# NixieClockDisplay.net
KiCad netlist of a schematic drawn in EAGLE
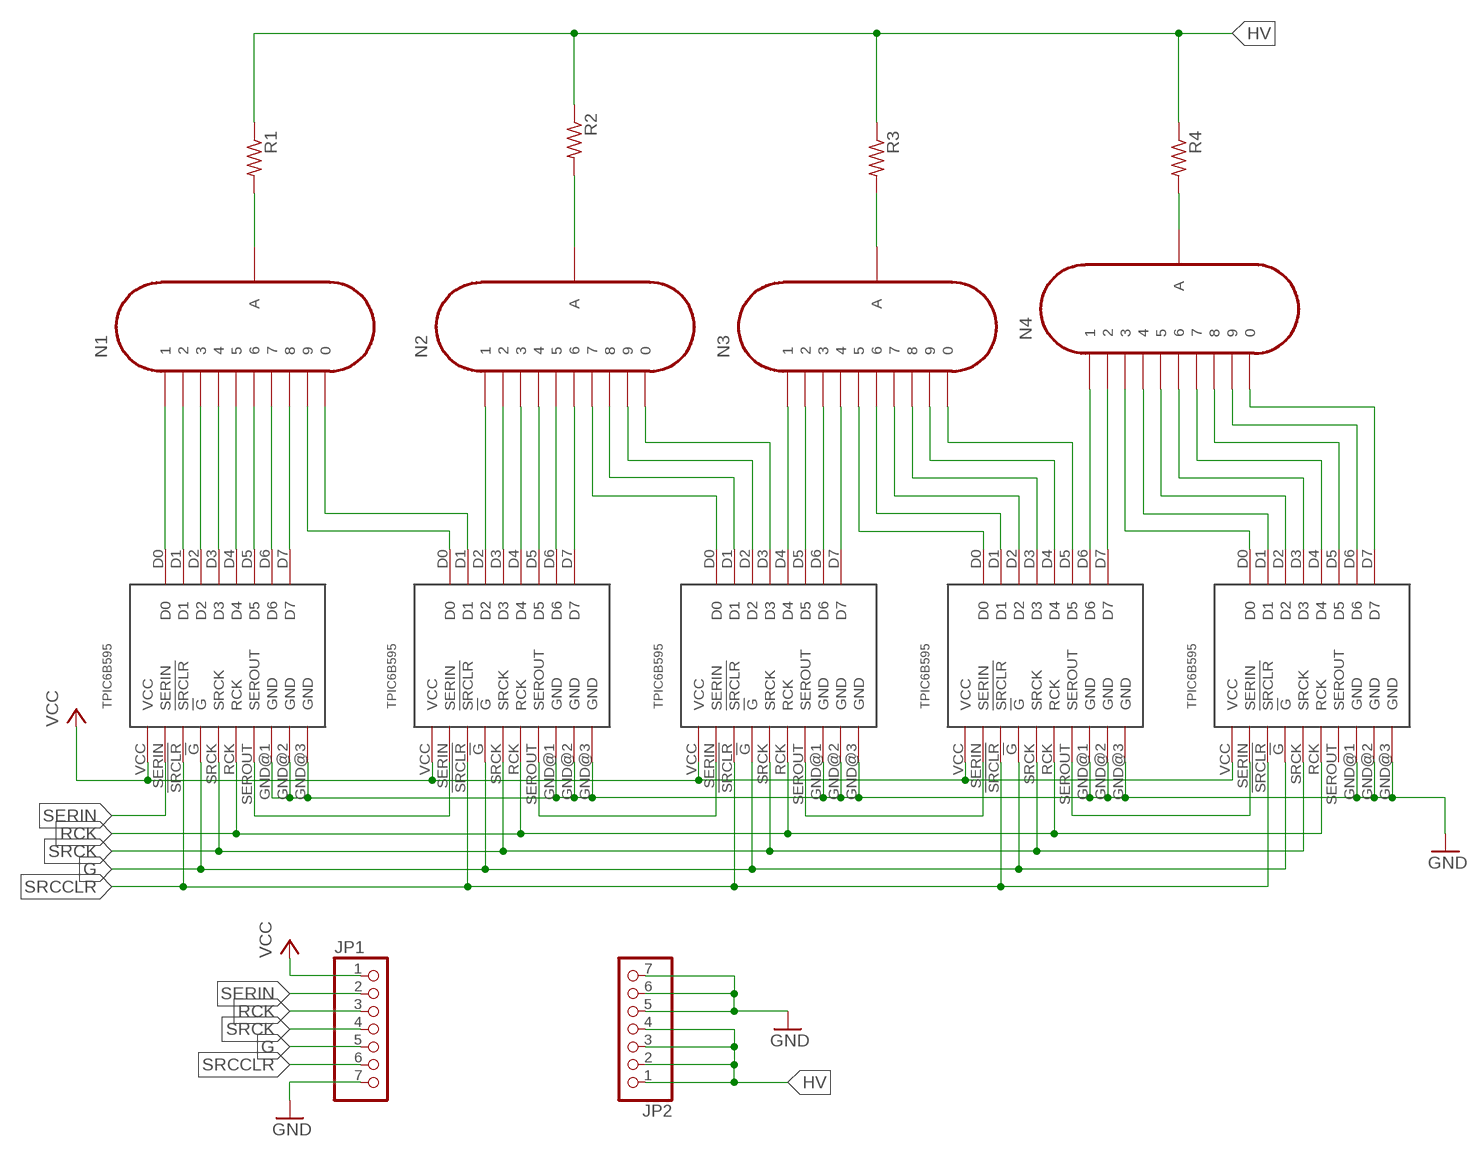
[diagram p0: schematic, sheet 1]

(export (version "E")
  (design (tool "Eeschema 10.0.6"))
  (components
    (comp (ref "JP1")
      (value "PINHD-1X7")
      (footprint "eagle-import:1X07")
      (libsource (lib "eagle-import") (part "PINHD-1X7"))
    )
    (comp (ref "JP2")
      (value "PINHD-1X7")
      (footprint "eagle-import:1X07")
      (libsource (lib "eagle-import") (part "PINHD-1X7"))
    )
    (comp (ref "N1")
      (value "IN-12A")
      (footprint "eagle-import:IN-12")
      (libsource (lib "eagle-import") (part "IN-12A"))
    )
    (comp (ref "N2")
      (value "IN-12A")
      (footprint "eagle-import:IN-12")
      (libsource (lib "eagle-import") (part "IN-12A"))
    )
    (comp (ref "N3")
      (value "IN-12A")
      (footprint "eagle-import:IN-12")
      (libsource (lib "eagle-import") (part "IN-12A"))
    )
    (comp (ref "N4")
      (value "IN-12A")
      (footprint "eagle-import:IN-12")
      (libsource (lib "eagle-import") (part "IN-12A"))
    )
    (comp (ref "R1")
      (value "R-US_0207/10")
      (footprint "eagle-import:0207_10")
      (libsource (lib "eagle-import") (part "R-US_0207/10"))
    )
    (comp (ref "R2")
      (value "R-US_0207/10")
      (footprint "eagle-import:0207_10")
      (libsource (lib "eagle-import") (part "R-US_0207/10"))
    )
    (comp (ref "R3")
      (value "R-US_0207/10")
      (footprint "eagle-import:0207_10")
      (libsource (lib "eagle-import") (part "R-US_0207/10"))
    )
    (comp (ref "R4")
      (value "R-US_0207/10")
      (footprint "eagle-import:0207_10")
      (libsource (lib "eagle-import") (part "R-US_0207/10"))
    )
    (comp (ref "U$1")
      (value "TPIC6B595")
      (footprint "eagle-import:DIL20")
      (libsource (lib "eagle-import") (part "TPIC6B595"))
    )
    (comp (ref "U$2")
      (value "TPIC6B595")
      (footprint "eagle-import:DIL20")
      (libsource (lib "eagle-import") (part "TPIC6B595"))
    )
    (comp (ref "U$3")
      (value "TPIC6B595")
      (footprint "eagle-import:DIL20")
      (libsource (lib "eagle-import") (part "TPIC6B595"))
    )
    (comp (ref "U$4")
      (value "TPIC6B595")
      (footprint "eagle-import:DIL20")
      (libsource (lib "eagle-import") (part "TPIC6B595"))
    )
    (comp (ref "U$5")
      (value "TPIC6B595")
      (footprint "eagle-import:DIL20")
      (libsource (lib "eagle-import") (part "TPIC6B595"))
    )
  )
  (nets
    (net (code "1") (name "G") (class "Default")
      (node (ref "JP1") (pin "5") (pinfunction "5_5") (pintype "passive"))
      (node (ref "U$1") (pin "!G") (pinfunction "~{G}_!G") (pintype "bidirectional"))
      (node (ref "U$2") (pin "!G") (pinfunction "~{G}_!G") (pintype "bidirectional"))
      (node (ref "U$3") (pin "!G") (pinfunction "~{G}_!G") (pintype "bidirectional"))
      (node (ref "U$4") (pin "!G") (pinfunction "~{G}_!G") (pintype "bidirectional"))
      (node (ref "U$5") (pin "!G") (pinfunction "~{G}_!G") (pintype "bidirectional"))
    )
    (net (code "2") (name "GND") (class "Default")
      (node (ref "JP1") (pin "7") (pinfunction "7_7") (pintype "passive"))
      (node (ref "JP2") (pin "5") (pinfunction "5_5") (pintype "passive"))
      (node (ref "JP2") (pin "6") (pinfunction "6_6") (pintype "passive"))
      (node (ref "JP2") (pin "7") (pinfunction "7_7") (pintype "passive"))
      (node (ref "U$1") (pin "GND@1") (pinfunction "GND_GND@1") (pintype "bidirectional"))
      (node (ref "U$1") (pin "GND@2") (pinfunction "GND_GND@2") (pintype "bidirectional"))
      (node (ref "U$1") (pin "GND@3") (pinfunction "GND_GND@3") (pintype "bidirectional"))
      (node (ref "U$2") (pin "GND@1") (pinfunction "GND_GND@1") (pintype "bidirectional"))
      (node (ref "U$2") (pin "GND@2") (pinfunction "GND_GND@2") (pintype "bidirectional"))
      (node (ref "U$2") (pin "GND@3") (pinfunction "GND_GND@3") (pintype "bidirectional"))
      (node (ref "U$3") (pin "GND@1") (pinfunction "GND_GND@1") (pintype "bidirectional"))
      (node (ref "U$3") (pin "GND@2") (pinfunction "GND_GND@2") (pintype "bidirectional"))
      (node (ref "U$3") (pin "GND@3") (pinfunction "GND_GND@3") (pintype "bidirectional"))
      (node (ref "U$4") (pin "GND@1") (pinfunction "GND_GND@1") (pintype "bidirectional"))
      (node (ref "U$4") (pin "GND@2") (pinfunction "GND_GND@2") (pintype "bidirectional"))
      (node (ref "U$4") (pin "GND@3") (pinfunction "GND_GND@3") (pintype "bidirectional"))
      (node (ref "U$5") (pin "GND@1") (pinfunction "GND_GND@1") (pintype "bidirectional"))
      (node (ref "U$5") (pin "GND@2") (pinfunction "GND_GND@2") (pintype "bidirectional"))
      (node (ref "U$5") (pin "GND@3") (pinfunction "GND_GND@3") (pintype "bidirectional"))
    )
    (net (code "3") (name "HV") (class "Default")
      (node (ref "JP2") (pin "1") (pinfunction "1_1") (pintype "passive"))
      (node (ref "JP2") (pin "2") (pinfunction "2_2") (pintype "passive"))
      (node (ref "JP2") (pin "3") (pinfunction "3_3") (pintype "passive"))
      (node (ref "JP2") (pin "4") (pinfunction "4_4") (pintype "passive"))
      (node (ref "R1") (pin "1") (pinfunction "1_1") (pintype "passive"))
      (node (ref "R2") (pin "1") (pinfunction "1_1") (pintype "passive"))
      (node (ref "R3") (pin "1") (pinfunction "1_1") (pintype "passive"))
      (node (ref "R4") (pin "1") (pinfunction "1_1") (pintype "passive"))
    )
    (net (code "4") (name "Net-(N1-Pad0)") (class "Default")
      (node (ref "N1") (pin "0") (pinfunction "0_0") (pintype "bidirectional"))
      (node (ref "U$2") (pin "D1") (pinfunction "D1_D1") (pintype "bidirectional"))
    )
    (net (code "5") (name "Net-(N1-Pad1)") (class "Default")
      (node (ref "N1") (pin "1") (pinfunction "1_1") (pintype "bidirectional"))
      (node (ref "U$1") (pin "D0") (pinfunction "D0_D0") (pintype "bidirectional"))
    )
    (net (code "6") (name "Net-(N1-Pad2)") (class "Default")
      (node (ref "N1") (pin "2") (pinfunction "2_2") (pintype "bidirectional"))
      (node (ref "U$1") (pin "D1") (pinfunction "D1_D1") (pintype "bidirectional"))
    )
    (net (code "7") (name "Net-(N1-Pad3)") (class "Default")
      (node (ref "N1") (pin "3") (pinfunction "3_3") (pintype "bidirectional"))
      (node (ref "U$1") (pin "D2") (pinfunction "D2_D2") (pintype "bidirectional"))
    )
    (net (code "8") (name "Net-(N1-Pad4)") (class "Default")
      (node (ref "N1") (pin "4") (pinfunction "4_4") (pintype "bidirectional"))
      (node (ref "U$1") (pin "D3") (pinfunction "D3_D3") (pintype "bidirectional"))
    )
    (net (code "9") (name "Net-(N1-Pad5)") (class "Default")
      (node (ref "N1") (pin "5") (pinfunction "5_5") (pintype "bidirectional"))
      (node (ref "U$1") (pin "D4") (pinfunction "D4_D4") (pintype "bidirectional"))
    )
    (net (code "10") (name "Net-(N1-Pad6)") (class "Default")
      (node (ref "N1") (pin "6") (pinfunction "6_6") (pintype "bidirectional"))
      (node (ref "U$1") (pin "D5") (pinfunction "D5_D5") (pintype "bidirectional"))
    )
    (net (code "11") (name "Net-(N1-Pad7)") (class "Default")
      (node (ref "N1") (pin "7") (pinfunction "7_7") (pintype "bidirectional"))
      (node (ref "U$1") (pin "D6") (pinfunction "D6_D6") (pintype "bidirectional"))
    )
    (net (code "12") (name "Net-(N1-Pad8)") (class "Default")
      (node (ref "N1") (pin "8") (pinfunction "8_8") (pintype "bidirectional"))
      (node (ref "U$1") (pin "D7") (pinfunction "D7_D7") (pintype "bidirectional"))
    )
    (net (code "13") (name "Net-(N1-Pad9)") (class "Default")
      (node (ref "N1") (pin "9") (pinfunction "9_9") (pintype "bidirectional"))
      (node (ref "U$2") (pin "D0") (pinfunction "D0_D0") (pintype "bidirectional"))
    )
    (net (code "14") (name "Net-(N1-PadA)") (class "Default")
      (node (ref "N1") (pin "A") (pinfunction "A_A") (pintype "bidirectional"))
      (node (ref "R1") (pin "2") (pinfunction "2_2") (pintype "passive"))
    )
    (net (code "15") (name "Net-(N2-Pad0)") (class "Default")
      (node (ref "N2") (pin "0") (pinfunction "0_0") (pintype "bidirectional"))
      (node (ref "U$3") (pin "D3") (pinfunction "D3_D3") (pintype "bidirectional"))
    )
    (net (code "16") (name "Net-(N2-Pad1)") (class "Default")
      (node (ref "N2") (pin "1") (pinfunction "1_1") (pintype "bidirectional"))
      (node (ref "U$2") (pin "D2") (pinfunction "D2_D2") (pintype "bidirectional"))
    )
    (net (code "17") (name "Net-(N2-Pad2)") (class "Default")
      (node (ref "N2") (pin "2") (pinfunction "2_2") (pintype "bidirectional"))
      (node (ref "U$2") (pin "D3") (pinfunction "D3_D3") (pintype "bidirectional"))
    )
    (net (code "18") (name "Net-(N2-Pad3)") (class "Default")
      (node (ref "N2") (pin "3") (pinfunction "3_3") (pintype "bidirectional"))
      (node (ref "U$2") (pin "D4") (pinfunction "D4_D4") (pintype "bidirectional"))
    )
    (net (code "19") (name "Net-(N2-Pad4)") (class "Default")
      (node (ref "N2") (pin "4") (pinfunction "4_4") (pintype "bidirectional"))
      (node (ref "U$2") (pin "D5") (pinfunction "D5_D5") (pintype "bidirectional"))
    )
    (net (code "20") (name "Net-(N2-Pad5)") (class "Default")
      (node (ref "N2") (pin "5") (pinfunction "5_5") (pintype "bidirectional"))
      (node (ref "U$2") (pin "D6") (pinfunction "D6_D6") (pintype "bidirectional"))
    )
    (net (code "21") (name "Net-(N2-Pad6)") (class "Default")
      (node (ref "N2") (pin "6") (pinfunction "6_6") (pintype "bidirectional"))
      (node (ref "U$2") (pin "D7") (pinfunction "D7_D7") (pintype "bidirectional"))
    )
    (net (code "22") (name "Net-(N2-Pad7)") (class "Default")
      (node (ref "N2") (pin "7") (pinfunction "7_7") (pintype "bidirectional"))
      (node (ref "U$3") (pin "D0") (pinfunction "D0_D0") (pintype "bidirectional"))
    )
    (net (code "23") (name "Net-(N2-Pad8)") (class "Default")
      (node (ref "N2") (pin "8") (pinfunction "8_8") (pintype "bidirectional"))
      (node (ref "U$3") (pin "D1") (pinfunction "D1_D1") (pintype "bidirectional"))
    )
    (net (code "24") (name "Net-(N2-Pad9)") (class "Default")
      (node (ref "N2") (pin "9") (pinfunction "9_9") (pintype "bidirectional"))
      (node (ref "U$3") (pin "D2") (pinfunction "D2_D2") (pintype "bidirectional"))
    )
    (net (code "25") (name "Net-(N2-PadA)") (class "Default")
      (node (ref "N2") (pin "A") (pinfunction "A_A") (pintype "bidirectional"))
      (node (ref "R2") (pin "2") (pinfunction "2_2") (pintype "passive"))
    )
    (net (code "26") (name "Net-(N3-Pad0)") (class "Default")
      (node (ref "N3") (pin "0") (pinfunction "0_0") (pintype "bidirectional"))
      (node (ref "U$4") (pin "D5") (pinfunction "D5_D5") (pintype "bidirectional"))
    )
    (net (code "27") (name "Net-(N3-Pad1)") (class "Default")
      (node (ref "N3") (pin "1") (pinfunction "1_1") (pintype "bidirectional"))
      (node (ref "U$3") (pin "D4") (pinfunction "D4_D4") (pintype "bidirectional"))
    )
    (net (code "28") (name "Net-(N3-Pad2)") (class "Default")
      (node (ref "N3") (pin "2") (pinfunction "2_2") (pintype "bidirectional"))
      (node (ref "U$3") (pin "D5") (pinfunction "D5_D5") (pintype "bidirectional"))
    )
    (net (code "29") (name "Net-(N3-Pad3)") (class "Default")
      (node (ref "N3") (pin "3") (pinfunction "3_3") (pintype "bidirectional"))
      (node (ref "U$3") (pin "D6") (pinfunction "D6_D6") (pintype "bidirectional"))
    )
    (net (code "30") (name "Net-(N3-Pad4)") (class "Default")
      (node (ref "N3") (pin "4") (pinfunction "4_4") (pintype "bidirectional"))
      (node (ref "U$3") (pin "D7") (pinfunction "D7_D7") (pintype "bidirectional"))
    )
    (net (code "31") (name "Net-(N3-Pad5)") (class "Default")
      (node (ref "N3") (pin "5") (pinfunction "5_5") (pintype "bidirectional"))
      (node (ref "U$4") (pin "D0") (pinfunction "D0_D0") (pintype "bidirectional"))
    )
    (net (code "32") (name "Net-(N3-Pad6)") (class "Default")
      (node (ref "N3") (pin "6") (pinfunction "6_6") (pintype "bidirectional"))
      (node (ref "U$4") (pin "D1") (pinfunction "D1_D1") (pintype "bidirectional"))
    )
    (net (code "33") (name "Net-(N3-Pad7)") (class "Default")
      (node (ref "N3") (pin "7") (pinfunction "7_7") (pintype "bidirectional"))
      (node (ref "U$4") (pin "D2") (pinfunction "D2_D2") (pintype "bidirectional"))
    )
    (net (code "34") (name "Net-(N3-Pad8)") (class "Default")
      (node (ref "N3") (pin "8") (pinfunction "8_8") (pintype "bidirectional"))
      (node (ref "U$4") (pin "D3") (pinfunction "D3_D3") (pintype "bidirectional"))
    )
    (net (code "35") (name "Net-(N3-Pad9)") (class "Default")
      (node (ref "N3") (pin "9") (pinfunction "9_9") (pintype "bidirectional"))
      (node (ref "U$4") (pin "D4") (pinfunction "D4_D4") (pintype "bidirectional"))
    )
    (net (code "36") (name "Net-(N3-PadA)") (class "Default")
      (node (ref "N3") (pin "A") (pinfunction "A_A") (pintype "bidirectional"))
      (node (ref "R3") (pin "2") (pinfunction "2_2") (pintype "passive"))
    )
    (net (code "37") (name "Net-(N4-Pad0)") (class "Default")
      (node (ref "N4") (pin "0") (pinfunction "0_0") (pintype "bidirectional"))
      (node (ref "U$5") (pin "D7") (pinfunction "D7_D7") (pintype "bidirectional"))
    )
    (net (code "38") (name "Net-(N4-Pad1)") (class "Default")
      (node (ref "N4") (pin "1") (pinfunction "1_1") (pintype "bidirectional"))
      (node (ref "U$4") (pin "D6") (pinfunction "D6_D6") (pintype "bidirectional"))
    )
    (net (code "39") (name "Net-(N4-Pad2)") (class "Default")
      (node (ref "N4") (pin "2") (pinfunction "2_2") (pintype "bidirectional"))
      (node (ref "U$4") (pin "D7") (pinfunction "D7_D7") (pintype "bidirectional"))
    )
    (net (code "40") (name "Net-(N4-Pad3)") (class "Default")
      (node (ref "N4") (pin "3") (pinfunction "3_3") (pintype "bidirectional"))
      (node (ref "U$5") (pin "D0") (pinfunction "D0_D0") (pintype "bidirectional"))
    )
    (net (code "41") (name "Net-(N4-Pad4)") (class "Default")
      (node (ref "N4") (pin "4") (pinfunction "4_4") (pintype "bidirectional"))
      (node (ref "U$5") (pin "D1") (pinfunction "D1_D1") (pintype "bidirectional"))
    )
    (net (code "42") (name "Net-(N4-Pad5)") (class "Default")
      (node (ref "N4") (pin "5") (pinfunction "5_5") (pintype "bidirectional"))
      (node (ref "U$5") (pin "D2") (pinfunction "D2_D2") (pintype "bidirectional"))
    )
    (net (code "43") (name "Net-(N4-Pad6)") (class "Default")
      (node (ref "N4") (pin "6") (pinfunction "6_6") (pintype "bidirectional"))
      (node (ref "U$5") (pin "D3") (pinfunction "D3_D3") (pintype "bidirectional"))
    )
    (net (code "44") (name "Net-(N4-Pad7)") (class "Default")
      (node (ref "N4") (pin "7") (pinfunction "7_7") (pintype "bidirectional"))
      (node (ref "U$5") (pin "D4") (pinfunction "D4_D4") (pintype "bidirectional"))
    )
    (net (code "45") (name "Net-(N4-Pad8)") (class "Default")
      (node (ref "N4") (pin "8") (pinfunction "8_8") (pintype "bidirectional"))
      (node (ref "U$5") (pin "D5") (pinfunction "D5_D5") (pintype "bidirectional"))
    )
    (net (code "46") (name "Net-(N4-Pad9)") (class "Default")
      (node (ref "N4") (pin "9") (pinfunction "9_9") (pintype "bidirectional"))
      (node (ref "U$5") (pin "D6") (pinfunction "D6_D6") (pintype "bidirectional"))
    )
    (net (code "47") (name "Net-(N4-PadA)") (class "Default")
      (node (ref "N4") (pin "A") (pinfunction "A_A") (pintype "bidirectional"))
      (node (ref "R4") (pin "2") (pinfunction "2_2") (pintype "passive"))
    )
    (net (code "48") (name "Net-(U$1-PadSEROUT)") (class "Default")
      (node (ref "U$1") (pin "SEROUT") (pinfunction "SEROUT_SEROUT") (pintype "bidirectional"))
      (node (ref "U$2") (pin "SERIN") (pinfunction "SERIN_SERIN") (pintype "bidirectional"))
    )
    (net (code "49") (name "Net-(U$2-PadSEROUT)") (class "Default")
      (node (ref "U$2") (pin "SEROUT") (pinfunction "SEROUT_SEROUT") (pintype "bidirectional"))
      (node (ref "U$3") (pin "SERIN") (pinfunction "SERIN_SERIN") (pintype "bidirectional"))
    )
    (net (code "50") (name "Net-(U$3-PadSEROUT)") (class "Default")
      (node (ref "U$3") (pin "SEROUT") (pinfunction "SEROUT_SEROUT") (pintype "bidirectional"))
      (node (ref "U$4") (pin "SERIN") (pinfunction "SERIN_SERIN") (pintype "bidirectional"))
    )
    (net (code "51") (name "Net-(U$4-PadSEROUT)") (class "Default")
      (node (ref "U$4") (pin "SEROUT") (pinfunction "SEROUT_SEROUT") (pintype "bidirectional"))
      (node (ref "U$5") (pin "SERIN") (pinfunction "SERIN_SERIN") (pintype "bidirectional"))
    )
    (net (code "52") (name "RCK") (class "Default")
      (node (ref "JP1") (pin "3") (pinfunction "3_3") (pintype "passive"))
      (node (ref "U$1") (pin "RCK") (pinfunction "RCK_RCK") (pintype "bidirectional"))
      (node (ref "U$2") (pin "RCK") (pinfunction "RCK_RCK") (pintype "bidirectional"))
      (node (ref "U$3") (pin "RCK") (pinfunction "RCK_RCK") (pintype "bidirectional"))
      (node (ref "U$4") (pin "RCK") (pinfunction "RCK_RCK") (pintype "bidirectional"))
      (node (ref "U$5") (pin "RCK") (pinfunction "RCK_RCK") (pintype "bidirectional"))
    )
    (net (code "53") (name "SERIN") (class "Default")
      (node (ref "JP1") (pin "2") (pinfunction "2_2") (pintype "passive"))
      (node (ref "U$1") (pin "SERIN") (pinfunction "SERIN_SERIN") (pintype "bidirectional"))
    )
    (net (code "54") (name "SRCCLR") (class "Default")
      (node (ref "JP1") (pin "6") (pinfunction "6_6") (pintype "passive"))
      (node (ref "U$1") (pin "!SRCLR") (pinfunction "~{SRCLR}_!SRCLR") (pintype "bidirectional"))
      (node (ref "U$2") (pin "!SRCLR") (pinfunction "~{SRCLR}_!SRCLR") (pintype "bidirectional"))
      (node (ref "U$3") (pin "!SRCLR") (pinfunction "~{SRCLR}_!SRCLR") (pintype "bidirectional"))
      (node (ref "U$4") (pin "!SRCLR") (pinfunction "~{SRCLR}_!SRCLR") (pintype "bidirectional"))
      (node (ref "U$5") (pin "!SRCLR") (pinfunction "~{SRCLR}_!SRCLR") (pintype "bidirectional"))
    )
    (net (code "55") (name "SRCK") (class "Default")
      (node (ref "JP1") (pin "4") (pinfunction "4_4") (pintype "passive"))
      (node (ref "U$1") (pin "SRCK") (pinfunction "SRCK_SRCK") (pintype "bidirectional"))
      (node (ref "U$2") (pin "SRCK") (pinfunction "SRCK_SRCK") (pintype "bidirectional"))
      (node (ref "U$3") (pin "SRCK") (pinfunction "SRCK_SRCK") (pintype "bidirectional"))
      (node (ref "U$4") (pin "SRCK") (pinfunction "SRCK_SRCK") (pintype "bidirectional"))
      (node (ref "U$5") (pin "SRCK") (pinfunction "SRCK_SRCK") (pintype "bidirectional"))
    )
    (net (code "56") (name "VCC") (class "Default")
      (node (ref "JP1") (pin "1") (pinfunction "1_1") (pintype "passive"))
      (node (ref "U$1") (pin "VCC") (pinfunction "VCC_VCC") (pintype "bidirectional"))
      (node (ref "U$2") (pin "VCC") (pinfunction "VCC_VCC") (pintype "bidirectional"))
      (node (ref "U$3") (pin "VCC") (pinfunction "VCC_VCC") (pintype "bidirectional"))
      (node (ref "U$4") (pin "VCC") (pinfunction "VCC_VCC") (pintype "bidirectional"))
      (node (ref "U$5") (pin "VCC") (pinfunction "VCC_VCC") (pintype "bidirectional"))
    )
    (net (code "57") (name "unconnected-(U$5-PadSEROUT)") (class "Default")
      (node (ref "U$5") (pin "SEROUT") (pinfunction "SEROUT_SEROUT") (pintype "bidirectional"))
    )
  )
)
